# LED_Display.net
KiCad netlist of a schematic drawn in EAGLE
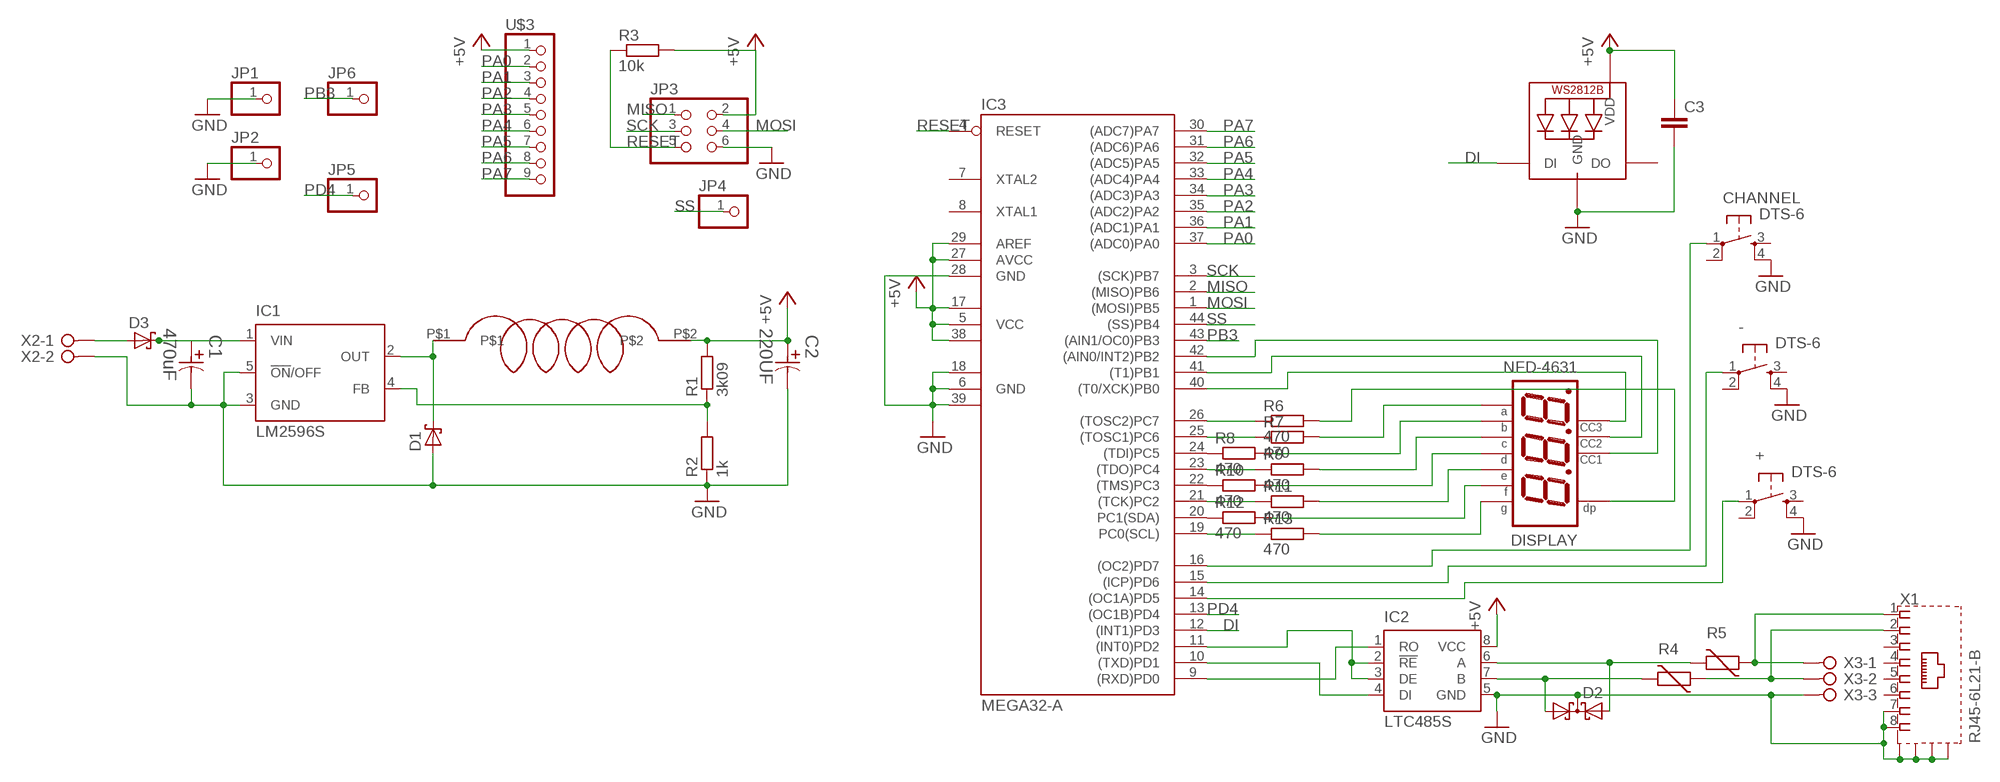
[diagram p0: schematic, sheet 1]

(export (version "E")
  (design (tool "Eeschema 10.0.6"))
  (components
    (comp (ref "+")
      (value "DTS-6")
      (footprint "eagle-import:DTS-6")
      (libsource (lib "eagle-import") (part "DTS-6"))
    )
    (comp (ref "-")
      (value "DTS-6")
      (footprint "eagle-import:DTS-6")
      (libsource (lib "eagle-import") (part "DTS-6"))
    )
    (comp (ref "C1")
      (value "470uF")
      (footprint "eagle-import:CAPAE1030X1050N")
      (fields
        (field (name "MPN") "EEE-FT1V561AP")
        (field (name "TOLERANCE") "±20 %")
        (field (name "OC_FARNELL") "2309060RL")
      )
      (libsource (lib "eagle-import") (part "EEE--CASE-GFT1V561AP"))
    )
    (comp (ref "C2")
      (value "220UF")
      (footprint "eagle-import:CAPAE660X610N")
      (fields (field (name "MPN") "EEE-FT1C221AP") (field (name "TOLERANCE") "±20 %"))
      (libsource (lib "eagle-import") (part "EEE--CASE-DFT1C221AP"))
    )
    (comp (ref "C3")
      (value "C-EUC0805")
      (footprint "eagle-import:C0805")
      (libsource (lib "eagle-import") (part "C-EUC0805"))
    )
    (comp (ref "CHANNEL")
      (value "DTS-6")
      (footprint "eagle-import:DTS-6")
      (libsource (lib "eagle-import") (part "DTS-6"))
    )
    (comp (ref "D1")
      (value "MBRS130LT3")
      (footprint "eagle-import:SMB")
      (libsource (lib "eagle-import") (part "MBRS130LT3"))
    )
    (comp (ref "D2")
      (value "BAS40-05")
      (footprint "eagle-import:SOT23")
      (libsource (lib "eagle-import") (part "BAS40-05"))
    )
    (comp (ref "D3")
      (value "MBRS130LT3")
      (footprint "eagle-import:SMB")
      (libsource (lib "eagle-import") (part "MBRS130LT3"))
    )
    (comp (ref "DISPLAY")
      (value "NFD-4631")
      (footprint "eagle-import:NFD-5631")
      (libsource (lib "eagle-import") (part "NFD-4631"))
    )
    (comp (ref "IC1")
      (value "LM2596S")
      (footprint "eagle-import:TO263-5")
      (fields (field (name "MF") "NATIONAL SEMICONDUCTOR") (field (name "MPN") "LM2596S-ADJ/NOPB"))
      (libsource (lib "eagle-import") (part "LM2596S"))
    )
    (comp (ref "IC2")
      (value "LTC485S")
      (footprint "eagle-import:SOIC8")
      (fields (field (name "OC_FARNELL") "1564306"))
      (libsource (lib "eagle-import") (part "LTC485S"))
    )
    (comp (ref "IC3")
      (value "MEGA32-A")
      (footprint "eagle-import:TQFP44")
      (fields (field (name "MPN") "ATMEGA32-16AU"))
      (libsource (lib "eagle-import") (part "MEGA32-A"))
    )
    (comp (ref "JP1")
      (value "PINHD-1X1CB")
      (footprint "eagle-import:1X01-CLEANBIG")
      (libsource (lib "eagle-import") (part "PINHD-1X1CB"))
    )
    (comp (ref "JP2")
      (value "PINHD-1X1CB")
      (footprint "eagle-import:1X01-CLEANBIG")
      (libsource (lib "eagle-import") (part "PINHD-1X1CB"))
    )
    (comp (ref "JP3")
      (value "PINHD-2X3")
      (footprint "eagle-import:2X03")
      (libsource (lib "eagle-import") (part "PINHD-2X3"))
    )
    (comp (ref "JP4")
      (value "PINHD-1X1")
      (footprint "eagle-import:1X01")
      (libsource (lib "eagle-import") (part "pinhead_PINHD-1X1"))
    )
    (comp (ref "JP5")
      (value "PINHD-1X1CB")
      (footprint "eagle-import:1X01-CLEANBIG")
      (libsource (lib "eagle-import") (part "PINHD-1X1CB"))
    )
    (comp (ref "JP6")
      (value "PINHD-1X1CB")
      (footprint "eagle-import:1X01-CLEANBIG")
      (libsource (lib "eagle-import") (part "PINHD-1X1CB"))
    )
    (comp (ref "LED1")
      (value "WS2812B5050")
      (footprint "eagle-import:WS2812B")
      (libsource (lib "eagle-import") (part "WS2812B5050"))
    )
    (comp (ref "R1")
      (value "3k09")
      (footprint "eagle-import:M0805")
      (libsource (lib "eagle-import") (part "R-EU_M0805"))
    )
    (comp (ref "R2")
      (value "1k")
      (footprint "eagle-import:M0805")
      (libsource (lib "eagle-import") (part "R-EU_M0805"))
    )
    (comp (ref "R3")
      (value "10k")
      (footprint "eagle-import:M0805")
      (libsource (lib "eagle-import") (part "R-EU_M0805"))
    )
    (comp (ref "R4")
      (value "VARISTORCN1812")
      (footprint "eagle-import:CT_CN1812")
      (libsource (lib "eagle-import") (part "VARISTORCN1812"))
    )
    (comp (ref "R5")
      (value "VARISTORCN1812")
      (footprint "eagle-import:CT_CN1812")
      (libsource (lib "eagle-import") (part "VARISTORCN1812"))
    )
    (comp (ref "R6")
      (value "470")
      (footprint "eagle-import:M0805")
      (libsource (lib "eagle-import") (part "R-EU_M0805"))
    )
    (comp (ref "R7")
      (value "470")
      (footprint "eagle-import:M0805")
      (libsource (lib "eagle-import") (part "R-EU_M0805"))
    )
    (comp (ref "R8")
      (value "470")
      (footprint "eagle-import:M0805")
      (libsource (lib "eagle-import") (part "R-EU_M0805"))
    )
    (comp (ref "R9")
      (value "470")
      (footprint "eagle-import:M0805")
      (libsource (lib "eagle-import") (part "R-EU_M0805"))
    )
    (comp (ref "R10")
      (value "470")
      (footprint "eagle-import:M0805")
      (libsource (lib "eagle-import") (part "R-EU_M0805"))
    )
    (comp (ref "R11")
      (value "470")
      (footprint "eagle-import:M0805")
      (libsource (lib "eagle-import") (part "R-EU_M0805"))
    )
    (comp (ref "R12")
      (value "470")
      (footprint "eagle-import:M0805")
      (libsource (lib "eagle-import") (part "R-EU_M0805"))
    )
    (comp (ref "R13")
      (value "470")
      (footprint "eagle-import:M0805")
      (libsource (lib "eagle-import") (part "R-EU_M0805"))
    )
    (comp (ref "U$1")
      (value "SRN8040")
      (footprint "eagle-import:SRN8040")
      (libsource (lib "eagle-import") (part "SRN8040"))
    )
    (comp (ref "U$3")
      (value "PINHD-1X9")
      (footprint "eagle-import:1X09-BIG")
      (libsource (lib "eagle-import") (part "PINHD-1X9"))
    )
    (comp (ref "X1")
      (value "RJ45-6L21-B")
      (footprint "eagle-import:RJ45-SHIELD1")
      (libsource (lib "eagle-import") (part "RJ4521-B-6L"))
    )
    (comp (ref "X2")
      (value "W237-02P")
      (footprint "eagle-import:W237-132")
      (libsource (lib "eagle-import") (part "W237-02P"))
    )
    (comp (ref "X3")
      (value "W237-03P")
      (footprint "eagle-import:W237-133")
      (libsource (lib "eagle-import") (part "W237-03P"))
    )
  )
  (nets
    (net (code "1") (name "+5V") (class "Default")
      (node (ref "C2") (pin "1") (pinfunction "1_1") (pintype "passive"))
      (node (ref "C3") (pin "1") (pinfunction "1_1") (pintype "passive"))
      (node (ref "IC2") (pin "8") (pinfunction "VCC_8") (pintype "input"))
      (node (ref "IC3") (pin "17") (pinfunction "VCC1_17") (pintype "power_in"))
      (node (ref "IC3") (pin "27") (pinfunction "AVCC_27") (pintype "power_in"))
      (node (ref "IC3") (pin "29") (pinfunction "AREF_29") (pintype "passive"))
      (node (ref "IC3") (pin "38") (pinfunction "VCC2_38") (pintype "power_in"))
      (node (ref "IC3") (pin "5") (pinfunction "VCC_5") (pintype "power_in"))
      (node (ref "JP3") (pin "2") (pinfunction "2_2") (pintype "passive"))
      (node (ref "LED1") (pin "1-VDD") (pinfunction "VDD_1-VDD") (pintype "power_in"))
      (node (ref "R1") (pin "2") (pinfunction "2_2") (pintype "passive"))
      (node (ref "R3") (pin "2") (pinfunction "2_2") (pintype "passive"))
      (node (ref "U$1") (pin "P$2") (pinfunction "P$2_P$2") (pintype "bidirectional"))
      (node (ref "U$3") (pin "1") (pinfunction "1_1") (pintype "passive"))
    )
    (net (code "2") (name "/DI") (class "Default")
      (node (ref "IC3") (pin "12") (pinfunction "(INT1)PD3_12") (pintype "bidirectional"))
      (node (ref "LED1") (pin "4-DIN") (pinfunction "DI_4-DIN") (pintype "input"))
    )
    (net (code "3") (name "/MISO") (class "Default")
      (node (ref "IC3") (pin "2") (pinfunction "(MISO)PB6_2") (pintype "bidirectional"))
      (node (ref "JP3") (pin "1") (pinfunction "1_1") (pintype "passive"))
    )
    (net (code "4") (name "/MOSI") (class "Default")
      (node (ref "IC3") (pin "1") (pinfunction "(MOSI)PB5_1") (pintype "bidirectional"))
      (node (ref "JP3") (pin "4") (pinfunction "4_4") (pintype "passive"))
    )
    (net (code "5") (name "/PA0") (class "Default")
      (node (ref "IC3") (pin "37") (pinfunction "(ADC0)PA0_37") (pintype "bidirectional"))
      (node (ref "U$3") (pin "2") (pinfunction "2_2") (pintype "passive"))
    )
    (net (code "6") (name "/PA1") (class "Default")
      (node (ref "IC3") (pin "36") (pinfunction "(ADC1)PA1_36") (pintype "bidirectional"))
      (node (ref "U$3") (pin "3") (pinfunction "3_3") (pintype "passive"))
    )
    (net (code "7") (name "/PA2") (class "Default")
      (node (ref "IC3") (pin "35") (pinfunction "(ADC2)PA2_35") (pintype "bidirectional"))
      (node (ref "U$3") (pin "4") (pinfunction "4_4") (pintype "passive"))
    )
    (net (code "8") (name "/PA3") (class "Default")
      (node (ref "IC3") (pin "34") (pinfunction "(ADC3)PA3_34") (pintype "bidirectional"))
      (node (ref "U$3") (pin "5") (pinfunction "5_5") (pintype "passive"))
    )
    (net (code "9") (name "/PA4") (class "Default")
      (node (ref "IC3") (pin "33") (pinfunction "(ADC4)PA4_33") (pintype "bidirectional"))
      (node (ref "U$3") (pin "6") (pinfunction "6_6") (pintype "passive"))
    )
    (net (code "10") (name "/PA5") (class "Default")
      (node (ref "IC3") (pin "32") (pinfunction "(ADC5)PA5_32") (pintype "bidirectional"))
      (node (ref "U$3") (pin "7") (pinfunction "7_7") (pintype "passive"))
    )
    (net (code "11") (name "/PA6") (class "Default")
      (node (ref "IC3") (pin "31") (pinfunction "(ADC6)PA6_31") (pintype "bidirectional"))
      (node (ref "U$3") (pin "8") (pinfunction "8_8") (pintype "passive"))
    )
    (net (code "12") (name "/PA7") (class "Default")
      (node (ref "IC3") (pin "30") (pinfunction "(ADC7)PA7_30") (pintype "bidirectional"))
      (node (ref "U$3") (pin "9") (pinfunction "9_9") (pintype "passive"))
    )
    (net (code "13") (name "/PB3") (class "Default")
      (node (ref "IC3") (pin "43") (pinfunction "(AIN1/OC0)PB3_43") (pintype "bidirectional"))
      (node (ref "JP6") (pin "1") (pinfunction "1_1") (pintype "passive"))
    )
    (net (code "14") (name "/PD4") (class "Default")
      (node (ref "IC3") (pin "13") (pinfunction "(OC1B)PD4_13") (pintype "bidirectional"))
      (node (ref "JP5") (pin "1") (pinfunction "1_1") (pintype "passive"))
    )
    (net (code "15") (name "/RESET") (class "Default")
      (node (ref "IC3") (pin "4") (pinfunction "RESET_4") (pintype "input"))
      (node (ref "JP3") (pin "5") (pinfunction "5_5") (pintype "passive"))
      (node (ref "R3") (pin "1") (pinfunction "1_1") (pintype "passive"))
    )
    (net (code "16") (name "/SCK") (class "Default")
      (node (ref "IC3") (pin "3") (pinfunction "(SCK)PB7_3") (pintype "bidirectional"))
      (node (ref "JP3") (pin "3") (pinfunction "3_3") (pintype "passive"))
    )
    (net (code "17") (name "/SS") (class "Default")
      (node (ref "IC3") (pin "44") (pinfunction "(SS)PB4_44") (pintype "bidirectional"))
      (node (ref "JP4") (pin "1") (pinfunction "1_1") (pintype "passive"))
    )
    (net (code "18") (name "GND") (class "Default")
      (node (ref "+") (pin "4") (pinfunction "4_4") (pintype "passive"))
      (node (ref "-") (pin "4") (pinfunction "4_4") (pintype "passive"))
      (node (ref "C1") (pin "2") (pinfunction "2_2") (pintype "passive"))
      (node (ref "C2") (pin "2") (pinfunction "2_2") (pintype "passive"))
      (node (ref "C3") (pin "2") (pinfunction "2_2") (pintype "passive"))
      (node (ref "CHANNEL") (pin "4") (pinfunction "4_4") (pintype "passive"))
      (node (ref "D1") (pin "A") (pinfunction "A_A") (pintype "passive"))
      (node (ref "D2") (pin "3") (pinfunction "C_3") (pintype "passive"))
      (node (ref "IC1") (pin "3") (pinfunction "GND_3") (pintype "power_in"))
      (node (ref "IC1") (pin "5") (pinfunction "~{ON}/OFF_5") (pintype "input"))
      (node (ref "IC2") (pin "5") (pinfunction "GND_5") (pintype "input"))
      (node (ref "IC3") (pin "18") (pinfunction "GND1_18") (pintype "power_in"))
      (node (ref "IC3") (pin "28") (pinfunction "GND_28") (pintype "power_in"))
      (node (ref "IC3") (pin "39") (pinfunction "GND2_39") (pintype "power_in"))
      (node (ref "IC3") (pin "6") (pinfunction "GND_6") (pintype "power_in"))
      (node (ref "JP1") (pin "1") (pinfunction "1_1") (pintype "passive"))
      (node (ref "JP2") (pin "1") (pinfunction "1_1") (pintype "passive"))
      (node (ref "JP3") (pin "6") (pinfunction "6_6") (pintype "passive"))
      (node (ref "LED1") (pin "3-GND") (pinfunction "GND_3-GND") (pintype "power_in"))
      (node (ref "R2") (pin "1") (pinfunction "1_1") (pintype "passive"))
      (node (ref "X1") (pin "7") (pinfunction "7_7") (pintype "passive"))
      (node (ref "X1") (pin "8") (pinfunction "8_8") (pintype "passive"))
      (node (ref "X1") (pin "S1") (pinfunction "S_S1") (pintype "passive"))
      (node (ref "X1") (pin "S2") (pinfunction "S_S2") (pintype "passive"))
      (node (ref "X1") (pin "S3") (pinfunction "S_S3") (pintype "passive"))
      (node (ref "X1") (pin "S4") (pinfunction "S_S4") (pintype "passive"))
      (node (ref "X2") (pin "2") (pinfunction "KL_2") (pintype "passive"))
      (node (ref "X3") (pin "3") (pinfunction "KL_3") (pintype "passive"))
    )
    (net (code "19") (name "Net-(D2-A1)") (class "Default")
      (node (ref "D2") (pin "1") (pinfunction "A1_1") (pintype "passive"))
      (node (ref "IC2") (pin "7") (pinfunction "B_7") (pintype "bidirectional"))
      (node (ref "R4") (pin "2") (pinfunction "2_2") (pintype "passive"))
    )
    (net (code "20") (name "Net-(D2-A2)") (class "Default")
      (node (ref "D2") (pin "2") (pinfunction "A2_2") (pintype "passive"))
      (node (ref "IC2") (pin "6") (pinfunction "A_6") (pintype "bidirectional"))
      (node (ref "R5") (pin "2") (pinfunction "2_2") (pintype "passive"))
    )
    (net (code "21") (name "Net-(DISPLAY-P$A)") (class "Default")
      (node (ref "DISPLAY") (pin "P$11") (pinfunction "P$A_P$11") (pintype "bidirectional"))
      (node (ref "R7") (pin "2") (pinfunction "2_2") (pintype "passive"))
    )
    (net (code "22") (name "Net-(DISPLAY-P$B)") (class "Default")
      (node (ref "DISPLAY") (pin "P$7") (pinfunction "P$B_P$7") (pintype "bidirectional"))
      (node (ref "R8") (pin "2") (pinfunction "2_2") (pintype "passive"))
    )
    (net (code "23") (name "Net-(DISPLAY-P$C)") (class "Default")
      (node (ref "DISPLAY") (pin "P$4") (pinfunction "P$C_P$4") (pintype "bidirectional"))
      (node (ref "R9") (pin "2") (pinfunction "2_2") (pintype "passive"))
    )
    (net (code "24") (name "Net-(DISPLAY-P$CC1)") (class "Default")
      (node (ref "DISPLAY") (pin "P$12") (pinfunction "P$CC1_P$12") (pintype "bidirectional"))
      (node (ref "IC3") (pin "42") (pinfunction "(AIN0/INT2)PB2_42") (pintype "bidirectional"))
    )
    (net (code "25") (name "Net-(DISPLAY-P$CC2)") (class "Default")
      (node (ref "DISPLAY") (pin "P$9") (pinfunction "P$CC2_P$9") (pintype "bidirectional"))
      (node (ref "IC3") (pin "41") (pinfunction "(T1)PB1_41") (pintype "bidirectional"))
    )
    (net (code "26") (name "Net-(DISPLAY-P$CC3)") (class "Default")
      (node (ref "DISPLAY") (pin "P$8") (pinfunction "P$CC3_P$8") (pintype "bidirectional"))
      (node (ref "IC3") (pin "40") (pinfunction "(T0/XCK)PB0_40") (pintype "bidirectional"))
    )
    (net (code "27") (name "Net-(DISPLAY-P$D)") (class "Default")
      (node (ref "DISPLAY") (pin "P$2") (pinfunction "P$D_P$2") (pintype "bidirectional"))
      (node (ref "R10") (pin "2") (pinfunction "2_2") (pintype "passive"))
    )
    (net (code "28") (name "Net-(DISPLAY-P$DP)") (class "Default")
      (node (ref "DISPLAY") (pin "P$3") (pinfunction "P$DP_P$3") (pintype "bidirectional"))
      (node (ref "R6") (pin "2") (pinfunction "2_2") (pintype "passive"))
    )
    (net (code "29") (name "Net-(DISPLAY-P$E)") (class "Default")
      (node (ref "DISPLAY") (pin "P$1") (pinfunction "P$E_P$1") (pintype "bidirectional"))
      (node (ref "R11") (pin "2") (pinfunction "2_2") (pintype "passive"))
    )
    (net (code "30") (name "Net-(DISPLAY-P$F)") (class "Default")
      (node (ref "DISPLAY") (pin "P$10") (pinfunction "P$F_P$10") (pintype "bidirectional"))
      (node (ref "R12") (pin "2") (pinfunction "2_2") (pintype "passive"))
    )
    (net (code "31") (name "Net-(DISPLAY-P$G)") (class "Default")
      (node (ref "DISPLAY") (pin "P$5") (pinfunction "P$G_P$5") (pintype "bidirectional"))
      (node (ref "R13") (pin "2") (pinfunction "2_2") (pintype "passive"))
    )
    (net (code "32") (name "Net-(IC1-FB)") (class "Default")
      (node (ref "IC1") (pin "4") (pinfunction "FB_4") (pintype "input"))
      (node (ref "R1") (pin "1") (pinfunction "1_1") (pintype "passive"))
      (node (ref "R2") (pin "2") (pinfunction "2_2") (pintype "passive"))
    )
    (net (code "33") (name "Net-(IC1-OUT)") (class "Default")
      (node (ref "D1") (pin "C") (pinfunction "C_C") (pintype "passive"))
      (node (ref "IC1") (pin "2") (pinfunction "OUT_2") (pintype "output"))
      (node (ref "U$1") (pin "P$1") (pinfunction "P$1_P$1") (pintype "bidirectional"))
    )
    (net (code "34") (name "Net-(IC1-VIN)") (class "Default")
      (node (ref "C1") (pin "1") (pinfunction "1_1") (pintype "passive"))
      (node (ref "D3") (pin "C") (pinfunction "C_C") (pintype "passive"))
      (node (ref "IC1") (pin "1") (pinfunction "VIN_1") (pintype "input"))
    )
    (net (code "35") (name "Net-(IC2-DE)") (class "Default")
      (node (ref "IC2") (pin "2") (pinfunction "~{RE}_2") (pintype "input"))
      (node (ref "IC2") (pin "3") (pinfunction "DE_3") (pintype "input"))
      (node (ref "IC3") (pin "11") (pinfunction "(INT0)PD2_11") (pintype "bidirectional"))
    )
    (net (code "36") (name "Net-(IC2-DI)") (class "Default")
      (node (ref "IC2") (pin "4") (pinfunction "DI_4") (pintype "input"))
      (node (ref "IC3") (pin "10") (pinfunction "(TXD)PD1_10") (pintype "bidirectional"))
    )
    (net (code "37") (name "Net-(IC2-RO)") (class "Default")
      (node (ref "IC2") (pin "1") (pinfunction "RO_1") (pintype "output"))
      (node (ref "IC3") (pin "9") (pinfunction "(RXD)PD0_9") (pintype "bidirectional"))
    )
    (net (code "38") (name "Net-(IC3-(ICP)PD6)") (class "Default")
      (node (ref "-") (pin "1") (pinfunction "1_1") (pintype "passive"))
      (node (ref "IC3") (pin "15") (pinfunction "(ICP)PD6_15") (pintype "bidirectional"))
    )
    (net (code "39") (name "Net-(IC3-(OC1A)PD5)") (class "Default")
      (node (ref "+") (pin "1") (pinfunction "1_1") (pintype "passive"))
      (node (ref "IC3") (pin "14") (pinfunction "(OC1A)PD5_14") (pintype "bidirectional"))
    )
    (net (code "40") (name "Net-(IC3-(OC2)PD7)") (class "Default")
      (node (ref "CHANNEL") (pin "1") (pinfunction "1_1") (pintype "passive"))
      (node (ref "IC3") (pin "16") (pinfunction "(OC2)PD7_16") (pintype "bidirectional"))
    )
    (net (code "41") (name "Net-(IC3-(TCK)PC2)") (class "Default")
      (node (ref "IC3") (pin "21") (pinfunction "(TCK)PC2_21") (pintype "bidirectional"))
      (node (ref "R11") (pin "1") (pinfunction "1_1") (pintype "passive"))
    )
    (net (code "42") (name "Net-(IC3-(TDI)PC5)") (class "Default")
      (node (ref "IC3") (pin "24") (pinfunction "(TDI)PC5_24") (pintype "bidirectional"))
      (node (ref "R8") (pin "1") (pinfunction "1_1") (pintype "passive"))
    )
    (net (code "43") (name "Net-(IC3-(TDO)PC4)") (class "Default")
      (node (ref "IC3") (pin "23") (pinfunction "(TDO)PC4_23") (pintype "bidirectional"))
      (node (ref "R9") (pin "1") (pinfunction "1_1") (pintype "passive"))
    )
    (net (code "44") (name "Net-(IC3-(TMS)PC3)") (class "Default")
      (node (ref "IC3") (pin "22") (pinfunction "(TMS)PC3_22") (pintype "bidirectional"))
      (node (ref "R10") (pin "1") (pinfunction "1_1") (pintype "passive"))
    )
    (net (code "45") (name "Net-(IC3-(TOSC1)PC6)") (class "Default")
      (node (ref "IC3") (pin "25") (pinfunction "(TOSC1)PC6_25") (pintype "bidirectional"))
      (node (ref "R7") (pin "1") (pinfunction "1_1") (pintype "passive"))
    )
    (net (code "46") (name "Net-(IC3-(TOSC2)PC7)") (class "Default")
      (node (ref "IC3") (pin "26") (pinfunction "(TOSC2)PC7_26") (pintype "bidirectional"))
      (node (ref "R6") (pin "1") (pinfunction "1_1") (pintype "passive"))
    )
    (net (code "47") (name "Net-(IC3-PC0(SCL))") (class "Default")
      (node (ref "IC3") (pin "19") (pinfunction "PC0(SCL)_19") (pintype "bidirectional"))
      (node (ref "R13") (pin "1") (pinfunction "1_1") (pintype "passive"))
    )
    (net (code "48") (name "Net-(IC3-PC1(SDA))") (class "Default")
      (node (ref "IC3") (pin "20") (pinfunction "PC1(SDA)_20") (pintype "bidirectional"))
      (node (ref "R12") (pin "1") (pinfunction "1_1") (pintype "passive"))
    )
    (net (code "49") (name "Net-(X2A-KL)") (class "Default")
      (node (ref "D3") (pin "A") (pinfunction "A_A") (pintype "passive"))
      (node (ref "X2") (pin "1") (pinfunction "KL_1") (pintype "passive"))
    )
    (net (code "50") (name "Net-(X3A-KL)") (class "Default")
      (node (ref "R5") (pin "1") (pinfunction "1_1") (pintype "passive"))
      (node (ref "X1") (pin "1") (pinfunction "1_1") (pintype "passive"))
      (node (ref "X3") (pin "1") (pinfunction "KL_1") (pintype "passive"))
    )
    (net (code "51") (name "Net-(X3B-KL)") (class "Default")
      (node (ref "R4") (pin "1") (pinfunction "1_1") (pintype "passive"))
      (node (ref "X1") (pin "2") (pinfunction "2_2") (pintype "passive"))
      (node (ref "X3") (pin "2") (pinfunction "KL_2") (pintype "passive"))
    )
    (net (code "52") (name "unconnected-(+-Pad2)") (class "Default")
      (node (ref "+") (pin "2") (pinfunction "2_2") (pintype "passive"))
    )
    (net (code "53") (name "unconnected-(+-Pad3)") (class "Default")
      (node (ref "+") (pin "3") (pinfunction "3_3") (pintype "passive"))
    )
    (net (code "54") (name "unconnected-(--Pad2)") (class "Default")
      (node (ref "-") (pin "2") (pinfunction "2_2") (pintype "passive"))
    )
    (net (code "55") (name "unconnected-(--Pad3)") (class "Default")
      (node (ref "-") (pin "3") (pinfunction "3_3") (pintype "passive"))
    )
    (net (code "56") (name "unconnected-(CHANNEL-Pad2)") (class "Default")
      (node (ref "CHANNEL") (pin "2") (pinfunction "2_2") (pintype "passive"))
    )
    (net (code "57") (name "unconnected-(CHANNEL-Pad3)") (class "Default")
      (node (ref "CHANNEL") (pin "3") (pinfunction "3_3") (pintype "passive"))
    )
    (net (code "58") (name "unconnected-(IC3-XTAL1-Pad8)") (class "Default")
      (node (ref "IC3") (pin "8") (pinfunction "XTAL1_8") (pintype "bidirectional"))
    )
    (net (code "59") (name "unconnected-(IC3-XTAL2-Pad7)") (class "Default")
      (node (ref "IC3") (pin "7") (pinfunction "XTAL2_7") (pintype "bidirectional"))
    )
    (net (code "60") (name "unconnected-(LED1-DO-Pad2-DOUT)") (class "Default")
      (node (ref "LED1") (pin "2-DOUT") (pinfunction "DO_2-DOUT") (pintype "output"))
    )
    (net (code "61") (name "unconnected-(X1-Pad3)") (class "Default")
      (node (ref "X1") (pin "3") (pinfunction "3_3") (pintype "passive"))
    )
    (net (code "62") (name "unconnected-(X1-Pad4)") (class "Default")
      (node (ref "X1") (pin "4") (pinfunction "4_4") (pintype "passive"))
    )
    (net (code "63") (name "unconnected-(X1-Pad5)") (class "Default")
      (node (ref "X1") (pin "5") (pinfunction "5_5") (pintype "passive"))
    )
    (net (code "64") (name "unconnected-(X1-Pad6)") (class "Default")
      (node (ref "X1") (pin "6") (pinfunction "6_6") (pintype "passive"))
    )
  )
)
